# NeoDigito_Small_v2_1_PCBWay.net
KiCad netlist of a schematic drawn in EAGLE
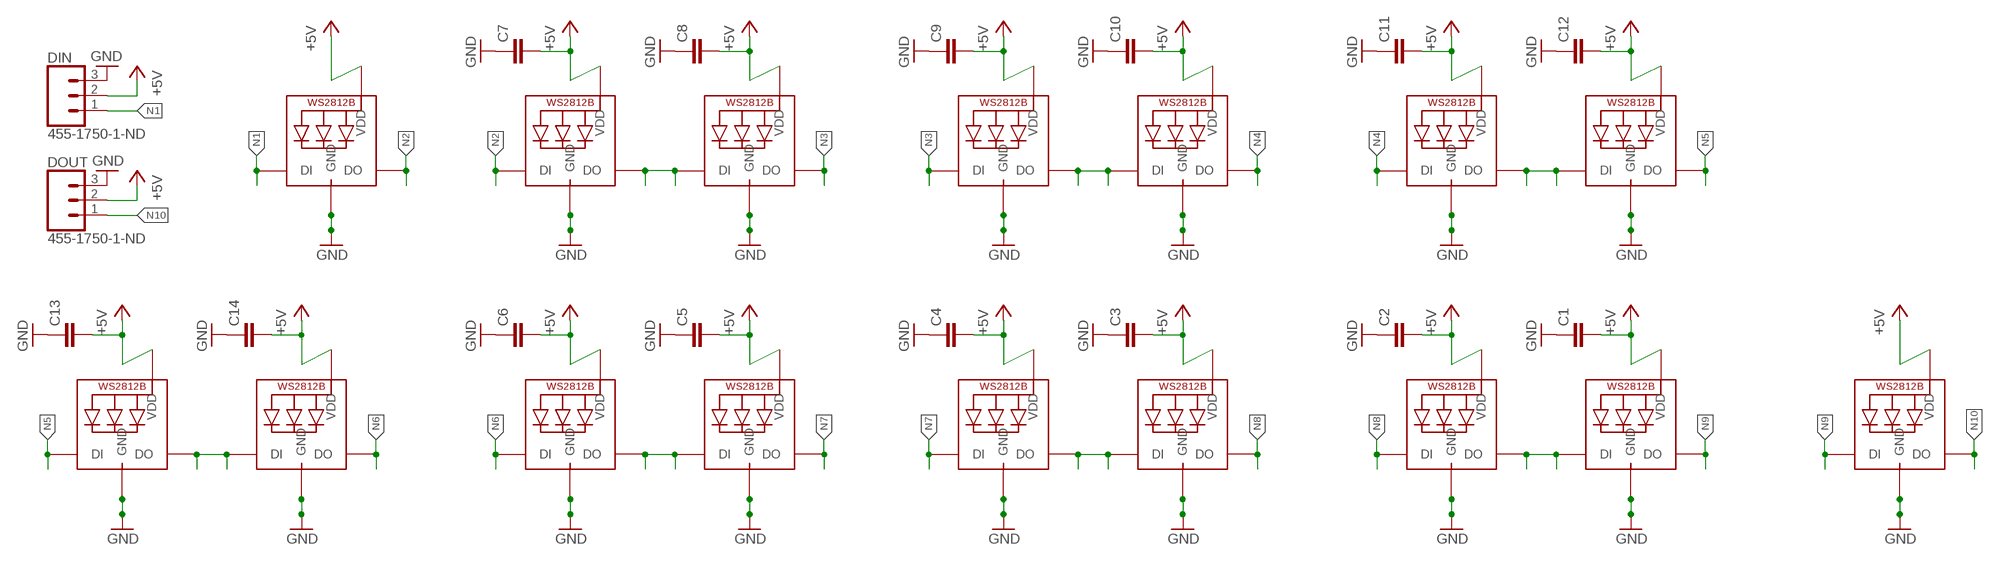
[diagram p0: schematic, sheet 1]

(export (version "E")
  (design (tool "Eeschema 10.0.6"))
  (components
    (comp (ref "C1")
      (value "C-EUC0805")
      (footprint "eagle-import:C0805")
      (libsource (lib "eagle-import") (part "C-EUC0805"))
    )
    (comp (ref "C2")
      (value "C-EUC0805")
      (footprint "eagle-import:C0805")
      (libsource (lib "eagle-import") (part "C-EUC0805"))
    )
    (comp (ref "C3")
      (value "C-EUC0805")
      (footprint "eagle-import:C0805")
      (libsource (lib "eagle-import") (part "C-EUC0805"))
    )
    (comp (ref "C4")
      (value "C-EUC0805")
      (footprint "eagle-import:C0805")
      (libsource (lib "eagle-import") (part "C-EUC0805"))
    )
    (comp (ref "C5")
      (value "C-EUC0805")
      (footprint "eagle-import:C0805")
      (libsource (lib "eagle-import") (part "C-EUC0805"))
    )
    (comp (ref "C6")
      (value "C-EUC0805")
      (footprint "eagle-import:C0805")
      (libsource (lib "eagle-import") (part "C-EUC0805"))
    )
    (comp (ref "C7")
      (value "C-EUC0805")
      (footprint "eagle-import:C0805")
      (libsource (lib "eagle-import") (part "C-EUC0805"))
    )
    (comp (ref "C8")
      (value "C-EUC0805")
      (footprint "eagle-import:C0805")
      (libsource (lib "eagle-import") (part "C-EUC0805"))
    )
    (comp (ref "C9")
      (value "C-EUC0805")
      (footprint "eagle-import:C0805")
      (libsource (lib "eagle-import") (part "C-EUC0805"))
    )
    (comp (ref "C10")
      (value "C-EUC0805")
      (footprint "eagle-import:C0805")
      (libsource (lib "eagle-import") (part "C-EUC0805"))
    )
    (comp (ref "C11")
      (value "C-EUC0805")
      (footprint "eagle-import:C0805")
      (libsource (lib "eagle-import") (part "C-EUC0805"))
    )
    (comp (ref "C12")
      (value "C-EUC0805")
      (footprint "eagle-import:C0805")
      (libsource (lib "eagle-import") (part "C-EUC0805"))
    )
    (comp (ref "C13")
      (value "C-EUC0805")
      (footprint "eagle-import:C0805")
      (libsource (lib "eagle-import") (part "C-EUC0805"))
    )
    (comp (ref "C14")
      (value "C-EUC0805")
      (footprint "eagle-import:C0805")
      (libsource (lib "eagle-import") (part "C-EUC0805"))
    )
    (comp (ref "DIN")
      (value "455-1750-1-ND")
      (footprint "eagle-import:1X03")
      (libsource (lib "eagle-import") (part "CONN_03"))
    )
    (comp (ref "DOUT")
      (value "455-1750-1-ND")
      (footprint "eagle-import:1X03_NO_SILK")
      (libsource (lib "eagle-import") (part "CONN_031X03_NO_SILK"))
    )
    (comp (ref "PA.")
      (value "WS2812B3535")
      (footprint "eagle-import:LED3535")
      (libsource (lib "eagle-import") (part "WS2812B3535"))
    )
    (comp (ref "PB.")
      (value "WS2812B3535")
      (footprint "eagle-import:LED3535")
      (libsource (lib "eagle-import") (part "WS2812B3535"))
    )
    (comp (ref "SA1.")
      (value "WS2812B3535")
      (footprint "eagle-import:LED3535")
      (libsource (lib "eagle-import") (part "WS2812B3535"))
    )
    (comp (ref "SA2.")
      (value "WS2812B3535")
      (footprint "eagle-import:LED3535")
      (libsource (lib "eagle-import") (part "WS2812B3535"))
    )
    (comp (ref "SB1.")
      (value "WS2812B3535")
      (footprint "eagle-import:LED3535")
      (libsource (lib "eagle-import") (part "WS2812B3535"))
    )
    (comp (ref "SB2.")
      (value "WS2812B3535")
      (footprint "eagle-import:LED3535")
      (libsource (lib "eagle-import") (part "WS2812B3535"))
    )
    (comp (ref "SC1.")
      (value "WS2812B3535")
      (footprint "eagle-import:LED3535")
      (libsource (lib "eagle-import") (part "WS2812B3535"))
    )
    (comp (ref "SC2.")
      (value "WS2812B3535")
      (footprint "eagle-import:LED3535")
      (libsource (lib "eagle-import") (part "WS2812B3535"))
    )
    (comp (ref "SD1.")
      (value "WS2812B3535")
      (footprint "eagle-import:LED3535")
      (libsource (lib "eagle-import") (part "WS2812B3535"))
    )
    (comp (ref "SD2.")
      (value "WS2812B3535")
      (footprint "eagle-import:LED3535")
      (libsource (lib "eagle-import") (part "WS2812B3535"))
    )
    (comp (ref "SE1.")
      (value "WS2812B3535")
      (footprint "eagle-import:LED3535")
      (libsource (lib "eagle-import") (part "WS2812B3535"))
    )
    (comp (ref "SE2.")
      (value "WS2812B3535")
      (footprint "eagle-import:LED3535")
      (libsource (lib "eagle-import") (part "WS2812B3535"))
    )
    (comp (ref "SF1.")
      (value "WS2812B3535")
      (footprint "eagle-import:LED3535")
      (libsource (lib "eagle-import") (part "WS2812B3535"))
    )
    (comp (ref "SF2.")
      (value "WS2812B3535")
      (footprint "eagle-import:LED3535")
      (libsource (lib "eagle-import") (part "WS2812B3535"))
    )
    (comp (ref "SG1.")
      (value "WS2812B3535")
      (footprint "eagle-import:LED3535")
      (libsource (lib "eagle-import") (part "WS2812B3535"))
    )
    (comp (ref "SG2.")
      (value "WS2812B3535")
      (footprint "eagle-import:LED3535")
      (libsource (lib "eagle-import") (part "WS2812B3535"))
    )
  )
  (nets
    (net (code "1") (name "+5V") (class "Default")
      (node (ref "C1") (pin "2") (pinfunction "2_2") (pintype "passive"))
      (node (ref "C10") (pin "2") (pinfunction "2_2") (pintype "passive"))
      (node (ref "C11") (pin "2") (pinfunction "2_2") (pintype "passive"))
      (node (ref "C12") (pin "2") (pinfunction "2_2") (pintype "passive"))
      (node (ref "C13") (pin "2") (pinfunction "2_2") (pintype "passive"))
      (node (ref "C14") (pin "2") (pinfunction "2_2") (pintype "passive"))
      (node (ref "C2") (pin "2") (pinfunction "2_2") (pintype "passive"))
      (node (ref "C3") (pin "2") (pinfunction "2_2") (pintype "passive"))
      (node (ref "C4") (pin "2") (pinfunction "2_2") (pintype "passive"))
      (node (ref "C5") (pin "2") (pinfunction "2_2") (pintype "passive"))
      (node (ref "C6") (pin "2") (pinfunction "2_2") (pintype "passive"))
      (node (ref "C7") (pin "2") (pinfunction "2_2") (pintype "passive"))
      (node (ref "C8") (pin "2") (pinfunction "2_2") (pintype "passive"))
      (node (ref "C9") (pin "2") (pinfunction "2_2") (pintype "passive"))
      (node (ref "DIN") (pin "2") (pinfunction "2_2") (pintype "passive"))
      (node (ref "DOUT") (pin "2") (pinfunction "2_2") (pintype "passive"))
      (node (ref "PA.") (pin "2") (pinfunction "VDD_2") (pintype "power_in"))
      (node (ref "PB.") (pin "2") (pinfunction "VDD_2") (pintype "power_in"))
      (node (ref "SA1.") (pin "2") (pinfunction "VDD_2") (pintype "power_in"))
      (node (ref "SA2.") (pin "2") (pinfunction "VDD_2") (pintype "power_in"))
      (node (ref "SB1.") (pin "2") (pinfunction "VDD_2") (pintype "power_in"))
      (node (ref "SB2.") (pin "2") (pinfunction "VDD_2") (pintype "power_in"))
      (node (ref "SC1.") (pin "2") (pinfunction "VDD_2") (pintype "power_in"))
      (node (ref "SC2.") (pin "2") (pinfunction "VDD_2") (pintype "power_in"))
      (node (ref "SD1.") (pin "2") (pinfunction "VDD_2") (pintype "power_in"))
      (node (ref "SD2.") (pin "2") (pinfunction "VDD_2") (pintype "power_in"))
      (node (ref "SE1.") (pin "2") (pinfunction "VDD_2") (pintype "power_in"))
      (node (ref "SE2.") (pin "2") (pinfunction "VDD_2") (pintype "power_in"))
      (node (ref "SF1.") (pin "2") (pinfunction "VDD_2") (pintype "power_in"))
      (node (ref "SF2.") (pin "2") (pinfunction "VDD_2") (pintype "power_in"))
      (node (ref "SG1.") (pin "2") (pinfunction "VDD_2") (pintype "power_in"))
      (node (ref "SG2.") (pin "2") (pinfunction "VDD_2") (pintype "power_in"))
    )
    (net (code "2") (name "GND") (class "Default")
      (node (ref "C1") (pin "1") (pinfunction "1_1") (pintype "passive"))
      (node (ref "C10") (pin "1") (pinfunction "1_1") (pintype "passive"))
      (node (ref "C11") (pin "1") (pinfunction "1_1") (pintype "passive"))
      (node (ref "C12") (pin "1") (pinfunction "1_1") (pintype "passive"))
      (node (ref "C13") (pin "1") (pinfunction "1_1") (pintype "passive"))
      (node (ref "C14") (pin "1") (pinfunction "1_1") (pintype "passive"))
      (node (ref "C2") (pin "1") (pinfunction "1_1") (pintype "passive"))
      (node (ref "C3") (pin "1") (pinfunction "1_1") (pintype "passive"))
      (node (ref "C4") (pin "1") (pinfunction "1_1") (pintype "passive"))
      (node (ref "C5") (pin "1") (pinfunction "1_1") (pintype "passive"))
      (node (ref "C6") (pin "1") (pinfunction "1_1") (pintype "passive"))
      (node (ref "C7") (pin "1") (pinfunction "1_1") (pintype "passive"))
      (node (ref "C8") (pin "1") (pinfunction "1_1") (pintype "passive"))
      (node (ref "C9") (pin "1") (pinfunction "1_1") (pintype "passive"))
      (node (ref "DIN") (pin "3") (pinfunction "3_3") (pintype "passive"))
      (node (ref "DOUT") (pin "3") (pinfunction "3_3") (pintype "passive"))
      (node (ref "PA.") (pin "4") (pinfunction "GND_4") (pintype "power_in"))
      (node (ref "PB.") (pin "4") (pinfunction "GND_4") (pintype "power_in"))
      (node (ref "SA1.") (pin "4") (pinfunction "GND_4") (pintype "power_in"))
      (node (ref "SA2.") (pin "4") (pinfunction "GND_4") (pintype "power_in"))
      (node (ref "SB1.") (pin "4") (pinfunction "GND_4") (pintype "power_in"))
      (node (ref "SB2.") (pin "4") (pinfunction "GND_4") (pintype "power_in"))
      (node (ref "SC1.") (pin "4") (pinfunction "GND_4") (pintype "power_in"))
      (node (ref "SC2.") (pin "4") (pinfunction "GND_4") (pintype "power_in"))
      (node (ref "SD1.") (pin "4") (pinfunction "GND_4") (pintype "power_in"))
      (node (ref "SD2.") (pin "4") (pinfunction "GND_4") (pintype "power_in"))
      (node (ref "SE1.") (pin "4") (pinfunction "GND_4") (pintype "power_in"))
      (node (ref "SE2.") (pin "4") (pinfunction "GND_4") (pintype "power_in"))
      (node (ref "SF1.") (pin "4") (pinfunction "GND_4") (pintype "power_in"))
      (node (ref "SF2.") (pin "4") (pinfunction "GND_4") (pintype "power_in"))
      (node (ref "SG1.") (pin "4") (pinfunction "GND_4") (pintype "power_in"))
      (node (ref "SG2.") (pin "4") (pinfunction "GND_4") (pintype "power_in"))
    )
    (net (code "3") (name "N1") (class "Default")
      (node (ref "DIN") (pin "1") (pinfunction "1_1") (pintype "passive"))
      (node (ref "PB.") (pin "1") (pinfunction "DI_1") (pintype "input"))
    )
    (net (code "4") (name "N2") (class "Default")
      (node (ref "PB.") (pin "3") (pinfunction "DO_3") (pintype "output"))
      (node (ref "SC1.") (pin "1") (pinfunction "DI_1") (pintype "input"))
    )
    (net (code "5") (name "N3") (class "Default")
      (node (ref "SC2.") (pin "3") (pinfunction "DO_3") (pintype "output"))
      (node (ref "SD1.") (pin "1") (pinfunction "DI_1") (pintype "input"))
    )
    (net (code "6") (name "N4") (class "Default")
      (node (ref "SD2.") (pin "3") (pinfunction "DO_3") (pintype "output"))
      (node (ref "SE1.") (pin "1") (pinfunction "DI_1") (pintype "input"))
    )
    (net (code "7") (name "N5") (class "Default")
      (node (ref "SE2.") (pin "3") (pinfunction "DO_3") (pintype "output"))
      (node (ref "SG1.") (pin "1") (pinfunction "DI_1") (pintype "input"))
    )
    (net (code "8") (name "N6") (class "Default")
      (node (ref "SB1.") (pin "1") (pinfunction "DI_1") (pintype "input"))
      (node (ref "SG2.") (pin "3") (pinfunction "DO_3") (pintype "output"))
    )
    (net (code "9") (name "N7") (class "Default")
      (node (ref "SA1.") (pin "1") (pinfunction "DI_1") (pintype "input"))
      (node (ref "SB2.") (pin "3") (pinfunction "DO_3") (pintype "output"))
    )
    (net (code "10") (name "N8") (class "Default")
      (node (ref "SA2.") (pin "3") (pinfunction "DO_3") (pintype "output"))
      (node (ref "SF1.") (pin "1") (pinfunction "DI_1") (pintype "input"))
    )
    (net (code "11") (name "N9") (class "Default")
      (node (ref "PA.") (pin "1") (pinfunction "DI_1") (pintype "input"))
      (node (ref "SF2.") (pin "3") (pinfunction "DO_3") (pintype "output"))
    )
    (net (code "12") (name "N10") (class "Default")
      (node (ref "DOUT") (pin "1") (pinfunction "1_1") (pintype "passive"))
      (node (ref "PA.") (pin "3") (pinfunction "DO_3") (pintype "output"))
    )
    (net (code "13") (name "Net-(SA1.-DO)") (class "Default")
      (node (ref "SA1.") (pin "3") (pinfunction "DO_3") (pintype "output"))
      (node (ref "SA2.") (pin "1") (pinfunction "DI_1") (pintype "input"))
    )
    (net (code "14") (name "Net-(SB1.-DO)") (class "Default")
      (node (ref "SB1.") (pin "3") (pinfunction "DO_3") (pintype "output"))
      (node (ref "SB2.") (pin "1") (pinfunction "DI_1") (pintype "input"))
    )
    (net (code "15") (name "Net-(SC1.-DO)") (class "Default")
      (node (ref "SC1.") (pin "3") (pinfunction "DO_3") (pintype "output"))
      (node (ref "SC2.") (pin "1") (pinfunction "DI_1") (pintype "input"))
    )
    (net (code "16") (name "Net-(SD1.-DO)") (class "Default")
      (node (ref "SD1.") (pin "3") (pinfunction "DO_3") (pintype "output"))
      (node (ref "SD2.") (pin "1") (pinfunction "DI_1") (pintype "input"))
    )
    (net (code "17") (name "Net-(SE1.-DO)") (class "Default")
      (node (ref "SE1.") (pin "3") (pinfunction "DO_3") (pintype "output"))
      (node (ref "SE2.") (pin "1") (pinfunction "DI_1") (pintype "input"))
    )
    (net (code "18") (name "Net-(SF1.-DO)") (class "Default")
      (node (ref "SF1.") (pin "3") (pinfunction "DO_3") (pintype "output"))
      (node (ref "SF2.") (pin "1") (pinfunction "DI_1") (pintype "input"))
    )
    (net (code "19") (name "Net-(SG1.-DO)") (class "Default")
      (node (ref "SG1.") (pin "3") (pinfunction "DO_3") (pintype "output"))
      (node (ref "SG2.") (pin "1") (pinfunction "DI_1") (pintype "input"))
    )
  )
)
